# 12V_Efuses1.net
KiCad netlist of a schematic drawn in Altium Designer
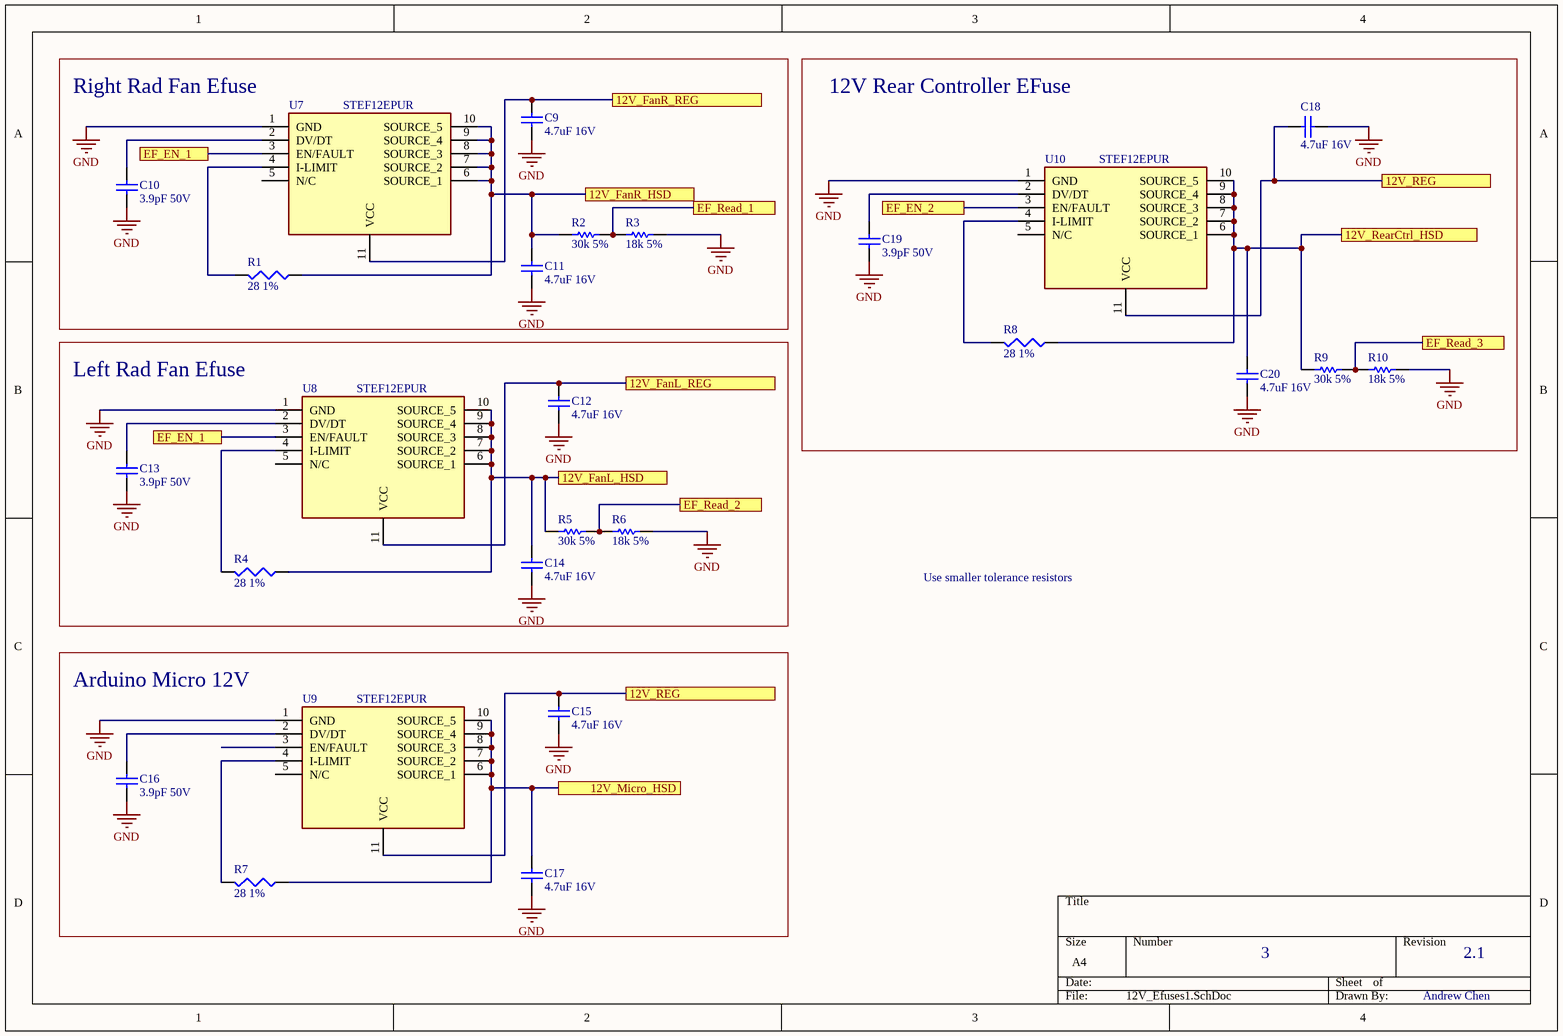
[diagram p0: 12V_Efuses1.SchDoc]

(export (version "E")
  (design (tool "Eeschema 10.0.6"))
  (components
    (comp (ref "C9")
      (value "4.7uF 16V")
      (footprint "C1206")
      (description "Capacitor (Semiconductor SIM Model)")
      (fields (field (name "PUBLISHER") "Altium Limited"))
      (libsource (lib "Miscellaneous Devices") (part "Cap Semi"))
    )
    (comp (ref "C10")
      (value "3.9pF 50V")
      (footprint "C1206")
      (description "Capacitor (Semiconductor SIM Model)")
      (fields (field (name "PUBLISHER") "Altium Limited"))
      (libsource (lib "Miscellaneous Devices") (part "Cap Semi"))
    )
    (comp (ref "C11")
      (value "4.7uF 16V")
      (footprint "C1206")
      (description "Capacitor (Semiconductor SIM Model)")
      (fields (field (name "PUBLISHER") "Altium Limited"))
      (libsource (lib "Miscellaneous Devices") (part "Cap Semi"))
    )
    (comp (ref "C12")
      (value "4.7uF 16V")
      (footprint "C1206")
      (description "Capacitor (Semiconductor SIM Model)")
      (fields (field (name "PUBLISHER") "Altium Limited"))
      (libsource (lib "Miscellaneous Devices") (part "Cap Semi"))
    )
    (comp (ref "C13")
      (value "3.9pF 50V")
      (footprint "C1206")
      (description "Capacitor (Semiconductor SIM Model)")
      (fields (field (name "PUBLISHER") "Altium Limited"))
      (libsource (lib "Miscellaneous Devices") (part "Cap Semi"))
    )
    (comp (ref "C14")
      (value "4.7uF 16V")
      (footprint "C1206")
      (description "Capacitor (Semiconductor SIM Model)")
      (fields (field (name "PUBLISHER") "Altium Limited"))
      (libsource (lib "Miscellaneous Devices") (part "Cap Semi"))
    )
    (comp (ref "C15")
      (value "4.7uF 16V")
      (footprint "C1206")
      (description "Capacitor (Semiconductor SIM Model)")
      (fields (field (name "PUBLISHER") "Altium Limited"))
      (libsource (lib "Miscellaneous Devices") (part "Cap Semi"))
    )
    (comp (ref "C16")
      (value "3.9pF 50V")
      (footprint "C1206")
      (description "Capacitor (Semiconductor SIM Model)")
      (fields (field (name "PUBLISHER") "Altium Limited"))
      (libsource (lib "Miscellaneous Devices") (part "Cap Semi"))
    )
    (comp (ref "C17")
      (value "4.7uF 16V")
      (footprint "C1206")
      (description "Capacitor (Semiconductor SIM Model)")
      (fields (field (name "PUBLISHER") "Altium Limited"))
      (libsource (lib "Miscellaneous Devices") (part "Cap Semi"))
    )
    (comp (ref "C18")
      (value "4.7uF 16V")
      (footprint "C1206")
      (description "Capacitor (Semiconductor SIM Model)")
      (fields (field (name "PUBLISHER") "Altium Limited"))
      (libsource (lib "Miscellaneous Devices") (part "Cap Semi"))
    )
    (comp (ref "C19")
      (value "3.9pF 50V")
      (footprint "C1206")
      (description "Capacitor (Semiconductor SIM Model)")
      (fields (field (name "PUBLISHER") "Altium Limited"))
      (libsource (lib "Miscellaneous Devices") (part "Cap Semi"))
    )
    (comp (ref "C20")
      (value "4.7uF 16V")
      (footprint "C1206")
      (description "Capacitor (Semiconductor SIM Model)")
      (fields (field (name "PUBLISHER") "Altium Limited"))
      (libsource (lib "Miscellaneous Devices") (part "Cap Semi"))
    )
    (comp (ref "R1")
      (value "28 1%")
      (footprint "J1-0603")
      (description "Resistor")
      (fields (field (name "PUBLISHER") "Altium Limited"))
      (libsource (lib "Miscellaneous Devices") (part "Res3"))
    )
    (comp (ref "R2")
      (value "30k 5%")
      (footprint "RESC1609X50X30NL8T20")
      (description "CRCW06030000Z0EA")
      (fields (field (name "MANUFACTURER") "Vishay Semiconductor"))
      (libsource (lib "Altium Content Vault") (part "RES-2"))
    )
    (comp (ref "R3")
      (value "18k 5%")
      (footprint "RESC1609X50X30NL8T20")
      (description "CRCW06030000Z0EA")
      (fields (field (name "MANUFACTURER") "Vishay Semiconductor"))
      (libsource (lib "Altium Content Vault") (part "RES-2"))
    )
    (comp (ref "R4")
      (value "28 1%")
      (footprint "J1-0603")
      (description "Resistor")
      (fields (field (name "PUBLISHER") "Altium Limited"))
      (libsource (lib "Miscellaneous Devices") (part "Res3"))
    )
    (comp (ref "R5")
      (value "30k 5%")
      (footprint "RESC1609X50X30NL8T20")
      (description "CRCW06030000Z0EA")
      (fields (field (name "MANUFACTURER") "Vishay Semiconductor"))
      (libsource (lib "Altium Content Vault") (part "RES-2"))
    )
    (comp (ref "R6")
      (value "18k 5%")
      (footprint "RESC1609X50X30NL8T20")
      (description "CRCW06030000Z0EA")
      (fields (field (name "MANUFACTURER") "Vishay Semiconductor"))
      (libsource (lib "Altium Content Vault") (part "RES-2"))
    )
    (comp (ref "R7")
      (value "28 1%")
      (footprint "J1-0603")
      (description "Resistor")
      (fields (field (name "PUBLISHER") "Altium Limited"))
      (libsource (lib "Miscellaneous Devices") (part "Res3"))
    )
    (comp (ref "R8")
      (value "28 1%")
      (footprint "J1-0603")
      (description "Resistor")
      (fields (field (name "PUBLISHER") "Altium Limited"))
      (libsource (lib "Miscellaneous Devices") (part "Res3"))
    )
    (comp (ref "R9")
      (value "30k 5%")
      (footprint "RESC1609X50X30NL8T20")
      (description "CRCW06030000Z0EA")
      (fields (field (name "MANUFACTURER") "Vishay Semiconductor"))
      (libsource (lib "Altium Content Vault") (part "RES-2"))
    )
    (comp (ref "R10")
      (value "18k 5%")
      (footprint "RESC1609X50X30NL8T20")
      (description "CRCW06030000Z0EA")
      (fields (field (name "MANUFACTURER") "Vishay Semiconductor"))
      (libsource (lib "Altium Content Vault") (part "RES-2"))
    )
    (comp (ref "U7")
      (value "STEF12EPUR")
      (footprint "SON50P300X300X100-11N-D")
      (description "Integrated Circuit")
      (fields (field (name "MOUSER PART NUMBER") "511-STEF12EPUR"))
      (libsource (lib "*") (part "STEF12EPUR"))
    )
    (comp (ref "U8")
      (value "STEF12EPUR")
      (footprint "SON50P300X300X100-11N-D")
      (description "Integrated Circuit")
      (fields (field (name "MOUSER PART NUMBER") "511-STEF12EPUR"))
      (libsource (lib "*") (part "STEF12EPUR"))
    )
    (comp (ref "U9")
      (value "STEF12EPUR")
      (footprint "SON50P300X300X100-11N-D")
      (description "Integrated Circuit")
      (fields (field (name "MOUSER PART NUMBER") "511-STEF12EPUR"))
      (libsource (lib "*") (part "STEF12EPUR"))
    )
    (comp (ref "U10")
      (value "STEF12EPUR")
      (footprint "SON50P300X300X100-11N-D")
      (description "Integrated Circuit")
      (fields (field (name "MOUSER PART NUMBER") "511-STEF12EPUR"))
      (libsource (lib "*") (part "STEF12EPUR"))
    )
  )
  (nets
    (net (code "1") (name "/12V_FanL_HSD") (class "Default")
      (node (ref "C14") (pin "1") (pinfunction "1_1") (pintype "passive"))
      (node (ref "R4") (pin "1") (pinfunction "1_1") (pintype "passive"))
      (node (ref "R5") (pin "1") (pinfunction "1_1") (pintype "passive"))
      (node (ref "U8") (pin "10") (pinfunction "SOURCE_5_10") (pintype "passive"))
      (node (ref "U8") (pin "6") (pinfunction "SOURCE_1_6") (pintype "passive"))
      (node (ref "U8") (pin "7") (pinfunction "SOURCE_2_7") (pintype "passive"))
      (node (ref "U8") (pin "8") (pinfunction "SOURCE_3_8") (pintype "passive"))
      (node (ref "U8") (pin "9") (pinfunction "SOURCE_4_9") (pintype "passive"))
    )
    (net (code "2") (name "/12V_FanL_REG") (class "Default")
      (node (ref "C12") (pin "1") (pinfunction "1_1") (pintype "passive"))
      (node (ref "U8") (pin "11") (pinfunction "VCC_11") (pintype "passive"))
    )
    (net (code "3") (name "/12V_FanR_HSD") (class "Default")
      (node (ref "C11") (pin "1") (pinfunction "1_1") (pintype "passive"))
      (node (ref "R1") (pin "1") (pinfunction "1_1") (pintype "passive"))
      (node (ref "R2") (pin "1") (pinfunction "1_1") (pintype "passive"))
      (node (ref "U7") (pin "10") (pinfunction "SOURCE_5_10") (pintype "passive"))
      (node (ref "U7") (pin "6") (pinfunction "SOURCE_1_6") (pintype "passive"))
      (node (ref "U7") (pin "7") (pinfunction "SOURCE_2_7") (pintype "passive"))
      (node (ref "U7") (pin "8") (pinfunction "SOURCE_3_8") (pintype "passive"))
      (node (ref "U7") (pin "9") (pinfunction "SOURCE_4_9") (pintype "passive"))
    )
    (net (code "4") (name "/12V_FanR_REG") (class "Default")
      (node (ref "C9") (pin "1") (pinfunction "1_1") (pintype "passive"))
      (node (ref "U7") (pin "11") (pinfunction "VCC_11") (pintype "passive"))
    )
    (net (code "5") (name "/12V_Micro_HSD") (class "Default")
      (node (ref "C17") (pin "1") (pinfunction "1_1") (pintype "passive"))
      (node (ref "R7") (pin "1") (pinfunction "1_1") (pintype "passive"))
      (node (ref "U9") (pin "10") (pinfunction "SOURCE_5_10") (pintype "passive"))
      (node (ref "U9") (pin "6") (pinfunction "SOURCE_1_6") (pintype "passive"))
      (node (ref "U9") (pin "7") (pinfunction "SOURCE_2_7") (pintype "passive"))
      (node (ref "U9") (pin "8") (pinfunction "SOURCE_3_8") (pintype "passive"))
      (node (ref "U9") (pin "9") (pinfunction "SOURCE_4_9") (pintype "passive"))
    )
    (net (code "6") (name "/12V_REG") (class "Default")
      (node (ref "C15") (pin "1") (pinfunction "1_1") (pintype "passive"))
      (node (ref "C18") (pin "2") (pinfunction "2_2") (pintype "passive"))
      (node (ref "U10") (pin "11") (pinfunction "VCC_11") (pintype "passive"))
      (node (ref "U9") (pin "11") (pinfunction "VCC_11") (pintype "passive"))
    )
    (net (code "7") (name "/12V_RearCtrl_HSD") (class "Default")
      (node (ref "C20") (pin "1") (pinfunction "1_1") (pintype "passive"))
      (node (ref "R8") (pin "1") (pinfunction "1_1") (pintype "passive"))
      (node (ref "R9") (pin "1") (pinfunction "1_1") (pintype "passive"))
      (node (ref "U10") (pin "10") (pinfunction "SOURCE_5_10") (pintype "passive"))
      (node (ref "U10") (pin "6") (pinfunction "SOURCE_1_6") (pintype "passive"))
      (node (ref "U10") (pin "7") (pinfunction "SOURCE_2_7") (pintype "passive"))
      (node (ref "U10") (pin "8") (pinfunction "SOURCE_3_8") (pintype "passive"))
      (node (ref "U10") (pin "9") (pinfunction "SOURCE_4_9") (pintype "passive"))
    )
    (net (code "8") (name "/EF_EN_1") (class "Default")
      (node (ref "U7") (pin "3") (pinfunction "EN/FAULT_3") (pintype "passive"))
      (node (ref "U8") (pin "3") (pinfunction "EN/FAULT_3") (pintype "passive"))
    )
    (net (code "9") (name "/EF_EN_2") (class "Default")
      (node (ref "U10") (pin "3") (pinfunction "EN/FAULT_3") (pintype "passive"))
    )
    (net (code "10") (name "/EF_Read_1") (class "Default")
      (node (ref "R2") (pin "2") (pinfunction "2_2") (pintype "passive"))
      (node (ref "R3") (pin "1") (pinfunction "1_1") (pintype "passive"))
    )
    (net (code "11") (name "/EF_Read_2") (class "Default")
      (node (ref "R5") (pin "2") (pinfunction "2_2") (pintype "passive"))
      (node (ref "R6") (pin "1") (pinfunction "1_1") (pintype "passive"))
    )
    (net (code "12") (name "/EF_Read_3") (class "Default")
      (node (ref "R10") (pin "1") (pinfunction "1_1") (pintype "passive"))
      (node (ref "R9") (pin "2") (pinfunction "2_2") (pintype "passive"))
    )
    (net (code "13") (name "GND") (class "Default")
      (node (ref "C10") (pin "2") (pinfunction "2_2") (pintype "passive"))
      (node (ref "C11") (pin "2") (pinfunction "2_2") (pintype "passive"))
      (node (ref "C12") (pin "2") (pinfunction "2_2") (pintype "passive"))
      (node (ref "C13") (pin "2") (pinfunction "2_2") (pintype "passive"))
      (node (ref "C14") (pin "2") (pinfunction "2_2") (pintype "passive"))
      (node (ref "C15") (pin "2") (pinfunction "2_2") (pintype "passive"))
      (node (ref "C16") (pin "2") (pinfunction "2_2") (pintype "passive"))
      (node (ref "C17") (pin "2") (pinfunction "2_2") (pintype "passive"))
      (node (ref "C18") (pin "1") (pinfunction "1_1") (pintype "passive"))
      (node (ref "C19") (pin "2") (pinfunction "2_2") (pintype "passive"))
      (node (ref "C20") (pin "2") (pinfunction "2_2") (pintype "passive"))
      (node (ref "C9") (pin "2") (pinfunction "2_2") (pintype "passive"))
      (node (ref "R10") (pin "2") (pinfunction "2_2") (pintype "passive"))
      (node (ref "R3") (pin "2") (pinfunction "2_2") (pintype "passive"))
      (node (ref "R6") (pin "2") (pinfunction "2_2") (pintype "passive"))
      (node (ref "U10") (pin "1") (pinfunction "GND_1") (pintype "passive"))
      (node (ref "U7") (pin "1") (pinfunction "GND_1") (pintype "passive"))
      (node (ref "U8") (pin "1") (pinfunction "GND_1") (pintype "passive"))
      (node (ref "U9") (pin "1") (pinfunction "GND_1") (pintype "passive"))
    )
    (net (code "14") (name "Net-(U7-DV{slash}DT)") (class "Default")
      (node (ref "C10") (pin "1") (pinfunction "1_1") (pintype "passive"))
      (node (ref "U7") (pin "2") (pinfunction "DV/DT_2") (pintype "passive"))
    )
    (net (code "15") (name "Net-(U7-I-LIMIT)") (class "Default")
      (node (ref "R1") (pin "2") (pinfunction "2_2") (pintype "passive"))
      (node (ref "U7") (pin "4") (pinfunction "I-LIMIT_4") (pintype "passive"))
    )
    (net (code "16") (name "Net-(U8-DV{slash}DT)") (class "Default")
      (node (ref "C13") (pin "1") (pinfunction "1_1") (pintype "passive"))
      (node (ref "U8") (pin "2") (pinfunction "DV/DT_2") (pintype "passive"))
    )
    (net (code "17") (name "Net-(U8-I-LIMIT)") (class "Default")
      (node (ref "R4") (pin "2") (pinfunction "2_2") (pintype "passive"))
      (node (ref "U8") (pin "4") (pinfunction "I-LIMIT_4") (pintype "passive"))
    )
    (net (code "18") (name "Net-(U9-DV{slash}DT)") (class "Default")
      (node (ref "C16") (pin "1") (pinfunction "1_1") (pintype "passive"))
      (node (ref "U9") (pin "2") (pinfunction "DV/DT_2") (pintype "passive"))
    )
    (net (code "19") (name "Net-(U9-I-LIMIT)") (class "Default")
      (node (ref "R7") (pin "2") (pinfunction "2_2") (pintype "passive"))
      (node (ref "U9") (pin "4") (pinfunction "I-LIMIT_4") (pintype "passive"))
    )
    (net (code "20") (name "Net-(U10-DV{slash}DT)") (class "Default")
      (node (ref "C19") (pin "1") (pinfunction "1_1") (pintype "passive"))
      (node (ref "U10") (pin "2") (pinfunction "DV/DT_2") (pintype "passive"))
    )
    (net (code "21") (name "Net-(U10-I-LIMIT)") (class "Default")
      (node (ref "R8") (pin "2") (pinfunction "2_2") (pintype "passive"))
      (node (ref "U10") (pin "4") (pinfunction "I-LIMIT_4") (pintype "passive"))
    )
    (net (code "22") (name "unconnected-(U7-N{slash}C-Pad5)") (class "Default")
      (node (ref "U7") (pin "5") (pinfunction "N/C_5") (pintype "passive"))
    )
    (net (code "23") (name "unconnected-(U8-N{slash}C-Pad5)") (class "Default")
      (node (ref "U8") (pin "5") (pinfunction "N/C_5") (pintype "passive"))
    )
    (net (code "24") (name "unconnected-(U9-EN{slash}FAULT-Pad3)") (class "Default")
      (node (ref "U9") (pin "3") (pinfunction "EN/FAULT_3") (pintype "passive"))
    )
    (net (code "25") (name "unconnected-(U9-N{slash}C-Pad5)") (class "Default")
      (node (ref "U9") (pin "5") (pinfunction "N/C_5") (pintype "passive"))
    )
    (net (code "26") (name "unconnected-(U10-N{slash}C-Pad5)") (class "Default")
      (node (ref "U10") (pin "5") (pinfunction "N/C_5") (pintype "passive"))
    )
  )
)
